# WiFi_5_Ray_Detector_v1.net
KiCad netlist of a schematic drawn in EAGLE
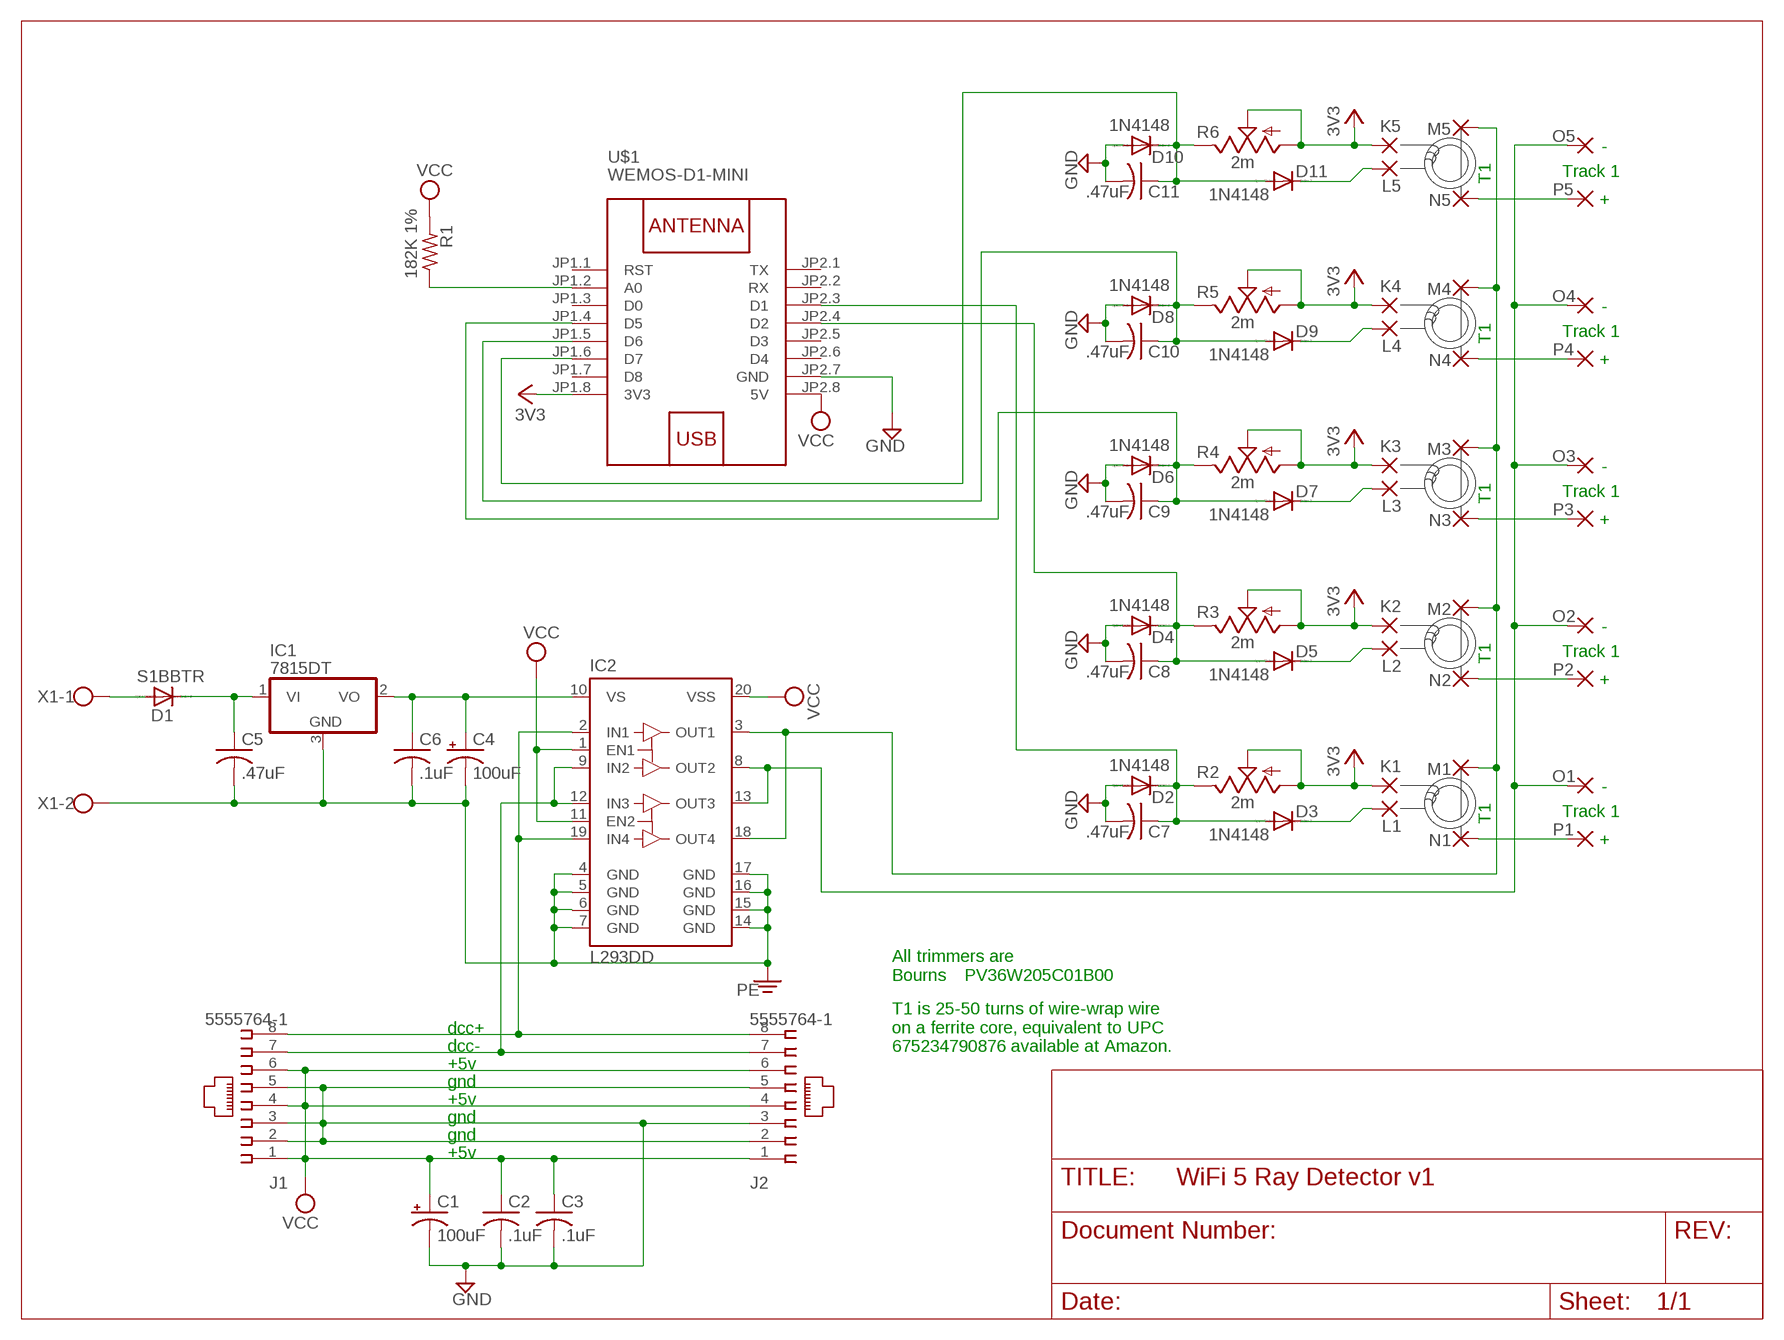
[diagram p0: schematic, sheet 1]

(export (version "E")
  (design (tool "Eeschema 10.0.6"))
  (components
    (comp (ref "C1")
      (value "100uF")
      (footprint "eagle-import:E3,5-8")
      (libsource (lib "eagle-import") (part "CPOL-USE3.5-8"))
    )
    (comp (ref "C2")
      (value ".1uF")
      (footprint "eagle-import:C1206")
      (libsource (lib "eagle-import") (part "C-USC1206"))
    )
    (comp (ref "C3")
      (value ".1uF")
      (footprint "eagle-import:C1206")
      (libsource (lib "eagle-import") (part "C-USC1206"))
    )
    (comp (ref "C4")
      (value "100uF")
      (footprint "eagle-import:E3,5-8")
      (libsource (lib "eagle-import") (part "CPOL-USE3.5-8"))
    )
    (comp (ref "C5")
      (value ".47uF")
      (footprint "eagle-import:C1206")
      (libsource (lib "eagle-import") (part "C-USC1206"))
    )
    (comp (ref "C6")
      (value ".1uF")
      (footprint "eagle-import:C1206")
      (libsource (lib "eagle-import") (part "C-USC1206"))
    )
    (comp (ref "C7")
      (value ".47uF")
      (footprint "eagle-import:C1206")
      (libsource (lib "eagle-import") (part "C-USC1206"))
    )
    (comp (ref "C8")
      (value ".47uF")
      (footprint "eagle-import:C1206")
      (libsource (lib "eagle-import") (part "C-USC1206"))
    )
    (comp (ref "C9")
      (value ".47uF")
      (footprint "eagle-import:C1206")
      (libsource (lib "eagle-import") (part "C-USC1206"))
    )
    (comp (ref "C10")
      (value ".47uF")
      (footprint "eagle-import:C1206")
      (libsource (lib "eagle-import") (part "C-USC1206"))
    )
    (comp (ref "C11")
      (value ".47uF")
      (footprint "eagle-import:C1206")
      (libsource (lib "eagle-import") (part "C-USC1206"))
    )
    (comp (ref "D1")
      (value "S1BBTR")
      (footprint "eagle-import:DO-214AC")
      (libsource (lib "eagle-import") (part "DIODE-DO-214AC"))
    )
    (comp (ref "D2")
      (value "1N4148")
      (footprint "eagle-import:SOD123")
      (libsource (lib "eagle-import") (part "DIODE-SOD123"))
    )
    (comp (ref "D3")
      (value "1N4148")
      (footprint "eagle-import:SOD123")
      (libsource (lib "eagle-import") (part "DIODE-SOD123"))
    )
    (comp (ref "D4")
      (value "1N4148")
      (footprint "eagle-import:SOD123")
      (libsource (lib "eagle-import") (part "DIODE-SOD123"))
    )
    (comp (ref "D5")
      (value "1N4148")
      (footprint "eagle-import:SOD123")
      (libsource (lib "eagle-import") (part "DIODE-SOD123"))
    )
    (comp (ref "D6")
      (value "1N4148")
      (footprint "eagle-import:SOD123")
      (libsource (lib "eagle-import") (part "DIODE-SOD123"))
    )
    (comp (ref "D7")
      (value "1N4148")
      (footprint "eagle-import:SOD123")
      (libsource (lib "eagle-import") (part "DIODE-SOD123"))
    )
    (comp (ref "D8")
      (value "1N4148")
      (footprint "eagle-import:SOD123")
      (libsource (lib "eagle-import") (part "DIODE-SOD123"))
    )
    (comp (ref "D9")
      (value "1N4148")
      (footprint "eagle-import:SOD123")
      (libsource (lib "eagle-import") (part "DIODE-SOD123"))
    )
    (comp (ref "D10")
      (value "1N4148")
      (footprint "eagle-import:SOD123")
      (libsource (lib "eagle-import") (part "DIODE-SOD123"))
    )
    (comp (ref "D11")
      (value "1N4148")
      (footprint "eagle-import:SOD123")
      (libsource (lib "eagle-import") (part "DIODE-SOD123"))
    )
    (comp (ref "IC1")
      (value "7815DT")
      (footprint "eagle-import:TO252")
      (libsource (lib "eagle-import") (part "78DT18"))
    )
    (comp (ref "IC2")
      (value "L293DD")
      (footprint "eagle-import:SO20")
      (libsource (lib "eagle-import") (part "L293DD"))
    )
    (comp (ref "J1")
      (value "5555764-1")
      (footprint "eagle-import:520426-4")
      (libsource (lib "eagle-import") (part "520426-4"))
    )
    (comp (ref "J2")
      (value "5555764-1")
      (footprint "eagle-import:520426-4")
      (libsource (lib "eagle-import") (part "520426-4"))
    )
    (comp (ref "K1")
      (value "2,15/1,0")
      (footprint "eagle-import:2,15_1,0")
      (libsource (lib "eagle-import") (part "2,15/1,0"))
    )
    (comp (ref "K2")
      (value "2,15/1,0")
      (footprint "eagle-import:2,15_1,0")
      (libsource (lib "eagle-import") (part "2,15/1,0"))
    )
    (comp (ref "K3")
      (value "2,15/1,0")
      (footprint "eagle-import:2,15_1,0")
      (libsource (lib "eagle-import") (part "2,15/1,0"))
    )
    (comp (ref "K4")
      (value "2,15/1,0")
      (footprint "eagle-import:2,15_1,0")
      (libsource (lib "eagle-import") (part "2,15/1,0"))
    )
    (comp (ref "K5")
      (value "2,15/1,0")
      (footprint "eagle-import:2,15_1,0")
      (libsource (lib "eagle-import") (part "2,15/1,0"))
    )
    (comp (ref "L1")
      (value "2,15/1,0")
      (footprint "eagle-import:2,15_1,0")
      (libsource (lib "eagle-import") (part "2,15/1,0"))
    )
    (comp (ref "L2")
      (value "2,15/1,0")
      (footprint "eagle-import:2,15_1,0")
      (libsource (lib "eagle-import") (part "2,15/1,0"))
    )
    (comp (ref "L3")
      (value "2,15/1,0")
      (footprint "eagle-import:2,15_1,0")
      (libsource (lib "eagle-import") (part "2,15/1,0"))
    )
    (comp (ref "L4")
      (value "2,15/1,0")
      (footprint "eagle-import:2,15_1,0")
      (libsource (lib "eagle-import") (part "2,15/1,0"))
    )
    (comp (ref "L5")
      (value "2,15/1,0")
      (footprint "eagle-import:2,15_1,0")
      (libsource (lib "eagle-import") (part "2,15/1,0"))
    )
    (comp (ref "M1")
      (value "NA")
      (footprint "eagle-import:2,15_1,0")
      (libsource (lib "eagle-import") (part "2,15/1,0"))
    )
    (comp (ref "M2")
      (value "NA")
      (footprint "eagle-import:2,15_1,0")
      (libsource (lib "eagle-import") (part "2,15/1,0"))
    )
    (comp (ref "M3")
      (value "NA")
      (footprint "eagle-import:2,15_1,0")
      (libsource (lib "eagle-import") (part "2,15/1,0"))
    )
    (comp (ref "M4")
      (value "NA")
      (footprint "eagle-import:2,15_1,0")
      (libsource (lib "eagle-import") (part "2,15/1,0"))
    )
    (comp (ref "M5")
      (value "NA")
      (footprint "eagle-import:2,15_1,0")
      (libsource (lib "eagle-import") (part "2,15/1,0"))
    )
    (comp (ref "N1")
      (value "NA")
      (footprint "eagle-import:2,15_1,0")
      (libsource (lib "eagle-import") (part "2,15/1,0"))
    )
    (comp (ref "N2")
      (value "NA")
      (footprint "eagle-import:2,15_1,0")
      (libsource (lib "eagle-import") (part "2,15/1,0"))
    )
    (comp (ref "N3")
      (value "NA")
      (footprint "eagle-import:2,15_1,0")
      (libsource (lib "eagle-import") (part "2,15/1,0"))
    )
    (comp (ref "N4")
      (value "NA")
      (footprint "eagle-import:2,15_1,0")
      (libsource (lib "eagle-import") (part "2,15/1,0"))
    )
    (comp (ref "N5")
      (value "NA")
      (footprint "eagle-import:2,15_1,0")
      (libsource (lib "eagle-import") (part "2,15/1,0"))
    )
    (comp (ref "O1")
      (value "NA")
      (footprint "eagle-import:2,15_1,0")
      (libsource (lib "eagle-import") (part "2,15/1,0"))
    )
    (comp (ref "O2")
      (value "NA")
      (footprint "eagle-import:2,15_1,0")
      (libsource (lib "eagle-import") (part "2,15/1,0"))
    )
    (comp (ref "O3")
      (value "NA")
      (footprint "eagle-import:2,15_1,0")
      (libsource (lib "eagle-import") (part "2,15/1,0"))
    )
    (comp (ref "O4")
      (value "NA")
      (footprint "eagle-import:2,15_1,0")
      (libsource (lib "eagle-import") (part "2,15/1,0"))
    )
    (comp (ref "O5")
      (value "NA")
      (footprint "eagle-import:2,15_1,0")
      (libsource (lib "eagle-import") (part "2,15/1,0"))
    )
    (comp (ref "P1")
      (value "NA")
      (footprint "eagle-import:2,15_1,0")
      (libsource (lib "eagle-import") (part "2,15/1,0"))
    )
    (comp (ref "P2")
      (value "NA")
      (footprint "eagle-import:2,15_1,0")
      (libsource (lib "eagle-import") (part "2,15/1,0"))
    )
    (comp (ref "P3")
      (value "NA")
      (footprint "eagle-import:2,15_1,0")
      (libsource (lib "eagle-import") (part "2,15/1,0"))
    )
    (comp (ref "P4")
      (value "NA")
      (footprint "eagle-import:2,15_1,0")
      (libsource (lib "eagle-import") (part "2,15/1,0"))
    )
    (comp (ref "P5")
      (value "NA")
      (footprint "eagle-import:2,15_1,0")
      (libsource (lib "eagle-import") (part "2,15/1,0"))
    )
    (comp (ref "R1")
      (value "182K 1%")
      (footprint "eagle-import:M1206")
      (libsource (lib "eagle-import") (part "R-US_M1206"))
    )
    (comp (ref "R2")
      (value "2m")
      (footprint "eagle-import:S63P")
      (libsource (lib "eagle-import") (part "TRIM_US-S63P"))
    )
    (comp (ref "R3")
      (value "2m")
      (footprint "eagle-import:S63P")
      (libsource (lib "eagle-import") (part "TRIM_US-S63P"))
    )
    (comp (ref "R4")
      (value "2m")
      (footprint "eagle-import:S63P")
      (libsource (lib "eagle-import") (part "TRIM_US-S63P"))
    )
    (comp (ref "R5")
      (value "2m")
      (footprint "eagle-import:S63P")
      (libsource (lib "eagle-import") (part "TRIM_US-S63P"))
    )
    (comp (ref "R6")
      (value "2m")
      (footprint "eagle-import:S63P")
      (libsource (lib "eagle-import") (part "TRIM_US-S63P"))
    )
    (comp (ref "U$1")
      (value "WEMOS-D1-MINI")
      (footprint "eagle-import:WEMOS-D1-MINI")
      (libsource (lib "eagle-import") (part "WEMOS-D1-MINI"))
    )
    (comp (ref "X1")
      (value "W237-102")
      (footprint "eagle-import:W237-102")
      (fields (field (name "MPN") "237-102"))
      (libsource (lib "eagle-import") (part "W237-102"))
    )
  )
  (nets
    (net (code "1") (name "3V3") (class "Default")
      (node (ref "K1") (pin "1") (pinfunction "P_1") (pintype "passive"))
      (node (ref "K2") (pin "1") (pinfunction "P_1") (pintype "passive"))
      (node (ref "K3") (pin "1") (pinfunction "P_1") (pintype "passive"))
      (node (ref "K4") (pin "1") (pinfunction "P_1") (pintype "passive"))
      (node (ref "K5") (pin "1") (pinfunction "P_1") (pintype "passive"))
      (node (ref "R2") (pin "A") (pinfunction "A_A") (pintype "passive"))
      (node (ref "R2") (pin "S") (pinfunction "S_S") (pintype "passive"))
      (node (ref "R3") (pin "A") (pinfunction "A_A") (pintype "passive"))
      (node (ref "R3") (pin "S") (pinfunction "S_S") (pintype "passive"))
      (node (ref "R4") (pin "A") (pinfunction "A_A") (pintype "passive"))
      (node (ref "R4") (pin "S") (pinfunction "S_S") (pintype "passive"))
      (node (ref "R5") (pin "A") (pinfunction "A_A") (pintype "passive"))
      (node (ref "R5") (pin "S") (pinfunction "S_S") (pintype "passive"))
      (node (ref "R6") (pin "A") (pinfunction "A_A") (pintype "passive"))
      (node (ref "R6") (pin "S") (pinfunction "S_S") (pintype "passive"))
      (node (ref "U$1") (pin "JP1.8") (pinfunction "3V3_JP1.8") (pintype "power_in"))
    )
    (net (code "2") (name "GND") (class "Default")
      (node (ref "C1") (pin "-") (pinfunction "-_-") (pintype "passive"))
      (node (ref "C10") (pin "2") (pinfunction "2_2") (pintype "passive"))
      (node (ref "C11") (pin "2") (pinfunction "2_2") (pintype "passive"))
      (node (ref "C2") (pin "2") (pinfunction "2_2") (pintype "passive"))
      (node (ref "C3") (pin "2") (pinfunction "2_2") (pintype "passive"))
      (node (ref "C7") (pin "2") (pinfunction "2_2") (pintype "passive"))
      (node (ref "C8") (pin "2") (pinfunction "2_2") (pintype "passive"))
      (node (ref "C9") (pin "2") (pinfunction "2_2") (pintype "passive"))
      (node (ref "D10") (pin "A") (pinfunction "A_A") (pintype "passive"))
      (node (ref "D2") (pin "A") (pinfunction "A_A") (pintype "passive"))
      (node (ref "D4") (pin "A") (pinfunction "A_A") (pintype "passive"))
      (node (ref "D6") (pin "A") (pinfunction "A_A") (pintype "passive"))
      (node (ref "D8") (pin "A") (pinfunction "A_A") (pintype "passive"))
      (node (ref "J1") (pin "2") (pinfunction "2_2") (pintype "passive"))
      (node (ref "J1") (pin "3") (pinfunction "3_3") (pintype "passive"))
      (node (ref "J1") (pin "5") (pinfunction "5_5") (pintype "passive"))
      (node (ref "J2") (pin "2") (pinfunction "2_2") (pintype "passive"))
      (node (ref "J2") (pin "3") (pinfunction "3_3") (pintype "passive"))
      (node (ref "J2") (pin "5") (pinfunction "5_5") (pintype "passive"))
      (node (ref "U$1") (pin "JP2.7") (pinfunction "GND_JP2.7") (pintype "power_in"))
    )
    (net (code "3") (name "Net-(IC1-VI)") (class "Default")
      (node (ref "C5") (pin "1") (pinfunction "1_1") (pintype "passive"))
      (node (ref "D1") (pin "C") (pinfunction "C_C") (pintype "passive"))
      (node (ref "IC1") (pin "1") (pinfunction "VI_1") (pintype "input"))
    )
    (net (code "4") (name "Net-(IC1-VO)") (class "Default")
      (node (ref "C4") (pin "+") (pinfunction "+_+") (pintype "passive"))
      (node (ref "C6") (pin "1") (pinfunction "1_1") (pintype "passive"))
      (node (ref "IC1") (pin "2") (pinfunction "VO_2") (pintype "passive"))
      (node (ref "IC2") (pin "10") (pinfunction "VS_10") (pintype "power_in"))
    )
    (net (code "5") (name "Net-(IC2-IN1)") (class "Default")
      (node (ref "IC2") (pin "19") (pinfunction "IN4_19") (pintype "input"))
      (node (ref "IC2") (pin "2") (pinfunction "IN1_2") (pintype "input"))
      (node (ref "J1") (pin "8") (pinfunction "8_8") (pintype "passive"))
      (node (ref "J2") (pin "8") (pinfunction "8_8") (pintype "passive"))
    )
    (net (code "6") (name "Net-(IC2-IN2)") (class "Default")
      (node (ref "IC2") (pin "12") (pinfunction "IN3_12") (pintype "input"))
      (node (ref "IC2") (pin "9") (pinfunction "IN2_9") (pintype "input"))
      (node (ref "J1") (pin "7") (pinfunction "7_7") (pintype "passive"))
      (node (ref "J2") (pin "7") (pinfunction "7_7") (pintype "passive"))
    )
    (net (code "7") (name "Net-(IC2-OUT1)") (class "Default")
      (node (ref "IC2") (pin "18") (pinfunction "OUT4_18") (pintype "output"))
      (node (ref "IC2") (pin "3") (pinfunction "OUT1_3") (pintype "output"))
      (node (ref "M1") (pin "1") (pinfunction "P_1") (pintype "passive"))
      (node (ref "M2") (pin "1") (pinfunction "P_1") (pintype "passive"))
      (node (ref "M3") (pin "1") (pinfunction "P_1") (pintype "passive"))
      (node (ref "M4") (pin "1") (pinfunction "P_1") (pintype "passive"))
      (node (ref "M5") (pin "1") (pinfunction "P_1") (pintype "passive"))
    )
    (net (code "8") (name "Net-(IC2-OUT2)") (class "Default")
      (node (ref "IC2") (pin "13") (pinfunction "OUT3_13") (pintype "output"))
      (node (ref "IC2") (pin "8") (pinfunction "OUT2_8") (pintype "output"))
      (node (ref "O1") (pin "1") (pinfunction "P_1") (pintype "passive"))
      (node (ref "O2") (pin "1") (pinfunction "P_1") (pintype "passive"))
      (node (ref "O3") (pin "1") (pinfunction "P_1") (pintype "passive"))
      (node (ref "O4") (pin "1") (pinfunction "P_1") (pintype "passive"))
      (node (ref "O5") (pin "1") (pinfunction "P_1") (pintype "passive"))
    )
    (net (code "9") (name "Net-(L1-P)") (class "Default")
      (node (ref "D3") (pin "C") (pinfunction "C_C") (pintype "passive"))
      (node (ref "L1") (pin "1") (pinfunction "P_1") (pintype "passive"))
    )
    (net (code "10") (name "Net-(L2-P)") (class "Default")
      (node (ref "D5") (pin "C") (pinfunction "C_C") (pintype "passive"))
      (node (ref "L2") (pin "1") (pinfunction "P_1") (pintype "passive"))
    )
    (net (code "11") (name "Net-(L3-P)") (class "Default")
      (node (ref "D7") (pin "C") (pinfunction "C_C") (pintype "passive"))
      (node (ref "L3") (pin "1") (pinfunction "P_1") (pintype "passive"))
    )
    (net (code "12") (name "Net-(L4-P)") (class "Default")
      (node (ref "D9") (pin "C") (pinfunction "C_C") (pintype "passive"))
      (node (ref "L4") (pin "1") (pinfunction "P_1") (pintype "passive"))
    )
    (net (code "13") (name "Net-(L5-P)") (class "Default")
      (node (ref "D11") (pin "C") (pinfunction "C_C") (pintype "passive"))
      (node (ref "L5") (pin "1") (pinfunction "P_1") (pintype "passive"))
    )
    (net (code "14") (name "Net-(N1-P)") (class "Default")
      (node (ref "N1") (pin "1") (pinfunction "P_1") (pintype "passive"))
      (node (ref "P1") (pin "1") (pinfunction "P_1") (pintype "passive"))
    )
    (net (code "15") (name "Net-(N2-P)") (class "Default")
      (node (ref "N2") (pin "1") (pinfunction "P_1") (pintype "passive"))
      (node (ref "P2") (pin "1") (pinfunction "P_1") (pintype "passive"))
    )
    (net (code "16") (name "Net-(N3-P)") (class "Default")
      (node (ref "N3") (pin "1") (pinfunction "P_1") (pintype "passive"))
      (node (ref "P3") (pin "1") (pinfunction "P_1") (pintype "passive"))
    )
    (net (code "17") (name "Net-(N4-P)") (class "Default")
      (node (ref "N4") (pin "1") (pinfunction "P_1") (pintype "passive"))
      (node (ref "P4") (pin "1") (pinfunction "P_1") (pintype "passive"))
    )
    (net (code "18") (name "Net-(N5-P)") (class "Default")
      (node (ref "N5") (pin "1") (pinfunction "P_1") (pintype "passive"))
      (node (ref "P5") (pin "1") (pinfunction "P_1") (pintype "passive"))
    )
    (net (code "19") (name "Net-(U$1-A0)") (class "Default")
      (node (ref "R1") (pin "1") (pinfunction "1_1") (pintype "passive"))
      (node (ref "U$1") (pin "JP1.2") (pinfunction "A0_JP1.2") (pintype "bidirectional"))
    )
    (net (code "20") (name "Net-(U$1-D1)") (class "Default")
      (node (ref "C7") (pin "1") (pinfunction "1_1") (pintype "passive"))
      (node (ref "D2") (pin "C") (pinfunction "C_C") (pintype "passive"))
      (node (ref "D3") (pin "A") (pinfunction "A_A") (pintype "passive"))
      (node (ref "R2") (pin "E") (pinfunction "E_E") (pintype "passive"))
      (node (ref "U$1") (pin "JP2.3") (pinfunction "D1_JP2.3") (pintype "bidirectional"))
    )
    (net (code "21") (name "Net-(U$1-D2)") (class "Default")
      (node (ref "C8") (pin "1") (pinfunction "1_1") (pintype "passive"))
      (node (ref "D4") (pin "C") (pinfunction "C_C") (pintype "passive"))
      (node (ref "D5") (pin "A") (pinfunction "A_A") (pintype "passive"))
      (node (ref "R3") (pin "E") (pinfunction "E_E") (pintype "passive"))
      (node (ref "U$1") (pin "JP2.4") (pinfunction "D2_JP2.4") (pintype "bidirectional"))
    )
    (net (code "22") (name "Net-(U$1-D5)") (class "Default")
      (node (ref "C9") (pin "1") (pinfunction "1_1") (pintype "passive"))
      (node (ref "D6") (pin "C") (pinfunction "C_C") (pintype "passive"))
      (node (ref "D7") (pin "A") (pinfunction "A_A") (pintype "passive"))
      (node (ref "R4") (pin "E") (pinfunction "E_E") (pintype "passive"))
      (node (ref "U$1") (pin "JP1.4") (pinfunction "D5_JP1.4") (pintype "bidirectional"))
    )
    (net (code "23") (name "Net-(U$1-D6)") (class "Default")
      (node (ref "C10") (pin "1") (pinfunction "1_1") (pintype "passive"))
      (node (ref "D8") (pin "C") (pinfunction "C_C") (pintype "passive"))
      (node (ref "D9") (pin "A") (pinfunction "A_A") (pintype "passive"))
      (node (ref "R5") (pin "E") (pinfunction "E_E") (pintype "passive"))
      (node (ref "U$1") (pin "JP1.5") (pinfunction "D6_JP1.5") (pintype "bidirectional"))
    )
    (net (code "24") (name "Net-(U$1-D7)") (class "Default")
      (node (ref "C11") (pin "1") (pinfunction "1_1") (pintype "passive"))
      (node (ref "D10") (pin "C") (pinfunction "C_C") (pintype "passive"))
      (node (ref "D11") (pin "A") (pinfunction "A_A") (pintype "passive"))
      (node (ref "R6") (pin "E") (pinfunction "E_E") (pintype "passive"))
      (node (ref "U$1") (pin "JP1.6") (pinfunction "D7_JP1.6") (pintype "bidirectional"))
    )
    (net (code "25") (name "Net-(X1A-KL)") (class "Default")
      (node (ref "D1") (pin "A") (pinfunction "A_A") (pintype "passive"))
      (node (ref "X1") (pin "1") (pinfunction "KL_1") (pintype "passive"))
    )
    (net (code "26") (name "PE") (class "Default")
      (node (ref "C4") (pin "-") (pinfunction "-_-") (pintype "passive"))
      (node (ref "C5") (pin "2") (pinfunction "2_2") (pintype "passive"))
      (node (ref "C6") (pin "2") (pinfunction "2_2") (pintype "passive"))
      (node (ref "IC1") (pin "3") (pinfunction "GND_3") (pintype "passive"))
      (node (ref "IC2") (pin "14") (pinfunction "GND_14") (pintype "power_in"))
      (node (ref "IC2") (pin "15") (pinfunction "GND_15") (pintype "power_in"))
      (node (ref "IC2") (pin "16") (pinfunction "GND_16") (pintype "power_in"))
      (node (ref "IC2") (pin "17") (pinfunction "GND_17") (pintype "power_in"))
      (node (ref "IC2") (pin "4") (pinfunction "GND_4") (pintype "power_in"))
      (node (ref "IC2") (pin "5") (pinfunction "GND_5") (pintype "power_in"))
      (node (ref "IC2") (pin "6") (pinfunction "GND_6") (pintype "power_in"))
      (node (ref "IC2") (pin "7") (pinfunction "GND_7") (pintype "power_in"))
      (node (ref "X1") (pin "2") (pinfunction "KL_2") (pintype "passive"))
    )
    (net (code "27") (name "VCC") (class "Default")
      (node (ref "C1") (pin "+") (pinfunction "+_+") (pintype "passive"))
      (node (ref "C2") (pin "1") (pinfunction "1_1") (pintype "passive"))
      (node (ref "C3") (pin "1") (pinfunction "1_1") (pintype "passive"))
      (node (ref "IC2") (pin "1") (pinfunction "EN1_1") (pintype "input"))
      (node (ref "IC2") (pin "11") (pinfunction "EN2_11") (pintype "input"))
      (node (ref "IC2") (pin "20") (pinfunction "VSS_20") (pintype "power_in"))
      (node (ref "J1") (pin "1") (pinfunction "1_1") (pintype "passive"))
      (node (ref "J1") (pin "4") (pinfunction "4_4") (pintype "passive"))
      (node (ref "J1") (pin "6") (pinfunction "6_6") (pintype "passive"))
      (node (ref "J2") (pin "1") (pinfunction "1_1") (pintype "passive"))
      (node (ref "J2") (pin "4") (pinfunction "4_4") (pintype "passive"))
      (node (ref "J2") (pin "6") (pinfunction "6_6") (pintype "passive"))
      (node (ref "R1") (pin "2") (pinfunction "2_2") (pintype "passive"))
      (node (ref "U$1") (pin "JP2.8") (pinfunction "5V_JP2.8") (pintype "power_in"))
    )
    (net (code "28") (name "unconnected-(U$1-D0-PadJP1.3)") (class "Default")
      (node (ref "U$1") (pin "JP1.3") (pinfunction "D0_JP1.3") (pintype "bidirectional"))
    )
    (net (code "29") (name "unconnected-(U$1-D3-PadJP2.5)") (class "Default")
      (node (ref "U$1") (pin "JP2.5") (pinfunction "D3_JP2.5") (pintype "bidirectional"))
    )
    (net (code "30") (name "unconnected-(U$1-D4-PadJP2.6)") (class "Default")
      (node (ref "U$1") (pin "JP2.6") (pinfunction "D4_JP2.6") (pintype "bidirectional"))
    )
    (net (code "31") (name "unconnected-(U$1-D8-PadJP1.7)") (class "Default")
      (node (ref "U$1") (pin "JP1.7") (pinfunction "D8_JP1.7") (pintype "bidirectional"))
    )
    (net (code "32") (name "unconnected-(U$1-RST-PadJP1.1)") (class "Default")
      (node (ref "U$1") (pin "JP1.1") (pinfunction "RST_JP1.1") (pintype "bidirectional"))
    )
    (net (code "33") (name "unconnected-(U$1-RX-PadJP2.2)") (class "Default")
      (node (ref "U$1") (pin "JP2.2") (pinfunction "RX_JP2.2") (pintype "bidirectional"))
    )
    (net (code "34") (name "unconnected-(U$1-TX-PadJP2.1)") (class "Default")
      (node (ref "U$1") (pin "JP2.1") (pinfunction "TX_JP2.1") (pintype "bidirectional"))
    )
  )
)
